# PATHOS_SOM_Ethernet.net
KiCad netlist of a schematic drawn in Altium Designer
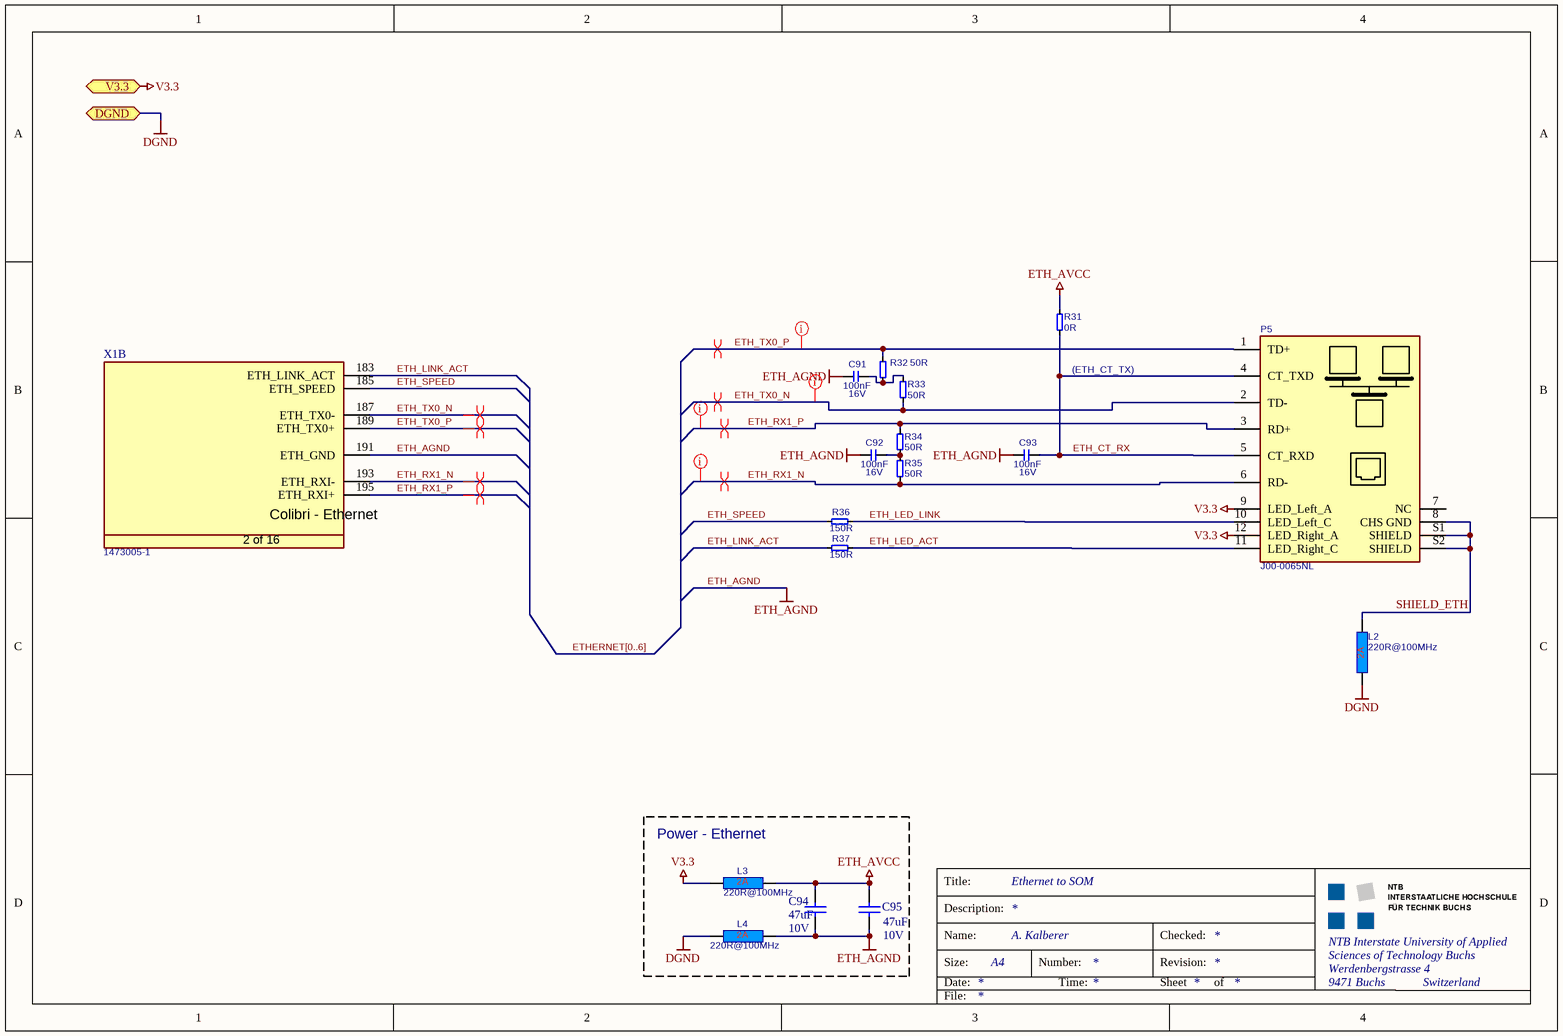
[diagram p0: PATHOS_SOM_Ethernet.SchDoc]

(export (version "E")
  (design (tool "Eeschema 10.0.6"))
  (components
    (comp (ref "C91")
      (value "100nF")
      (footprint "0603_3D")
      (description "Capacitor Ceramic X7R 100nF 16V 10% 0603")
      (fields (field (name "TOLERANCE") "10%") (field (name "RATING") "16V"))
      (libsource (lib "Viola") (part "C-X7R-100nF-16V-10%-0603"))
    )
    (comp (ref "C92")
      (value "100nF")
      (footprint "0603_3D")
      (description "Capacitor Ceramic X7R 100nF 16V 10% 0603")
      (fields (field (name "TOLERANCE") "10%") (field (name "RATING") "16V"))
      (libsource (lib "Viola") (part "C-X7R-100nF-16V-10%-0603"))
    )
    (comp (ref "C93")
      (value "100nF")
      (footprint "0603_3D")
      (description "Capacitor Ceramic X7R 100nF 16V 10% 0603")
      (fields (field (name "TOLERANCE") "10%") (field (name "RATING") "16V"))
      (libsource (lib "Viola") (part "C-X7R-100nF-16V-10%-0603"))
    )
    (comp (ref "C94")
      (value "47uF")
      (footprint "0805_3D")
      (description "Capacitor")
      (fields (field (name "VOLTAGE MAXIMUM") "10V") (field (name "#PUBLISHER") "Dr. A. Heinzelmann"))
      (libsource (lib "EFS_Sensorboard") (part "C"))
    )
    (comp (ref "C95")
      (value "47uF")
      (footprint "0805_3D")
      (description "Capacitor")
      (fields (field (name "VOLTAGE MAXIMUM") "10V") (field (name "#PUBLISHER") "Dr. A. Heinzelmann"))
      (libsource (lib "EFS_Sensorboard") (part "C"))
    )
    (comp (ref "L2")
      (value "220R@100MHz")
      (footprint "0603_3D")
      (description "220R@100MHz 2A EMI FILTER")
      (fields (field (name "TOLERANCE") "25%"))
      (libsource (lib "Viola") (part "L-220R@100MHz-2A-25%-0603"))
    )
    (comp (ref "L3")
      (value "220R@100MHz")
      (footprint "0603_3D")
      (description "220R@100MHz 2A EMI FILTER")
      (fields (field (name "TOLERANCE") "25%"))
      (libsource (lib "") (part "L-220R@100MHz-2A-25%-0603_1"))
    )
    (comp (ref "L4")
      (value "220R@100MHz")
      (footprint "0603_3D")
      (description "220R@100MHz 2A EMI FILTER")
      (fields (field (name "TOLERANCE") "25%"))
      (libsource (lib "") (part "L-220R@100MHz-2A-25%-0603_1"))
    )
    (comp (ref "P5")
      (value "J00-0065NL")
      (footprint "T_PULSE_J00-0065NL")
      (description "RJ45 Connector")
      (fields (field (name "MANUFACTURER PART NO.") "J00-0065NL"))
      (libsource (lib "Evaluation Board") (part "CON-Pulse-J00-0065NL"))
    )
    (comp (ref "R31")
      (value "0R")
      (footprint "0603_3D")
      (description "Resistor 0 ohm 100mW Jumper 0603")
      (fields (field (name "TOLERANCE") "1%"))
      (libsource (lib "Viola") (part "R-0R-100mW-JP-0603"))
    )
    (comp (ref "R32")
      (value "50R")
      (footprint "0603_3D")
      (description "Resistor 50 ohm 63mW 1% 0603")
      (fields (field (name "TOLERANCE") "1%"))
      (libsource (lib "Viola") (part "R-50R-63mW-1%-0603"))
    )
    (comp (ref "R33")
      (value "50R")
      (footprint "0603_3D")
      (description "Resistor 50 ohm 63mW 1% 0603")
      (fields (field (name "TOLERANCE") "1%"))
      (libsource (lib "Viola") (part "R-50R-63mW-1%-0603"))
    )
    (comp (ref "R34")
      (value "50R")
      (footprint "0603_3D")
      (description "Resistor 50 ohm 63mW 1% 0603")
      (fields (field (name "TOLERANCE") "1%"))
      (libsource (lib "Viola") (part "R-50R-63mW-1%-0603"))
    )
    (comp (ref "R35")
      (value "50R")
      (footprint "0603_3D")
      (description "Resistor 50 ohm 63mW 1% 0603")
      (fields (field (name "TOLERANCE") "1%"))
      (libsource (lib "Viola") (part "R-50R-63mW-1%-0603"))
    )
    (comp (ref "R36")
      (value "150R")
      (footprint "0603_3D")
      (description "Resistor 150 ohm 63mW 1% 0603")
      (fields (field (name "TOLERANCE") "1%"))
      (libsource (lib "Viola") (part "R-150R-63mW-1%-0603"))
    )
    (comp (ref "R37")
      (value "150R")
      (footprint "0603_3D")
      (description "Resistor 150 ohm 63mW 1% 0603")
      (fields (field (name "TOLERANCE") "1%"))
      (libsource (lib "Viola") (part "R-150R-63mW-1%-0603"))
    )
    (comp (ref "X1")
      (value "CON-Tyco-1473005-1-200-0.6mm")
      (footprint "T_Tyco_1473005-1")
      (description "SODIMM Connector")
      (fields (field (name "MANUFACTURER PART NO.") "1473005-1"))
      (libsource (lib "EFS_Sensorboard") (part "CON-Tyco-1473005-1-200-0.6mm"))
    )
  )
  (nets
    (net (code "9") (name "/ETH_CT_RX") (class "Default")
      (node (ref "C93") (pin "2") (pinfunction "2_2") (pintype "passive"))
      (node (ref "P5") (pin "4") (pinfunction "CT_TXD_4") (pintype "passive"))
      (node (ref "P5") (pin "5") (pinfunction "CT_RXD_5") (pintype "passive"))
      (node (ref "R31") (pin "2") (pinfunction "2_2") (pintype "passive"))
    )
    (net (code "10") (name "/ETH_LED_ACT") (class "Default")
      (node (ref "P5") (pin "11") (pinfunction "LED_Right_C_11") (pintype "passive"))
      (node (ref "R37") (pin "2") (pinfunction "2_2") (pintype "passive"))
    )
    (net (code "11") (name "/ETH_LED_LINK") (class "Default")
      (node (ref "P5") (pin "10") (pinfunction "LED_Left_C_10") (pintype "passive"))
      (node (ref "R36") (pin "2") (pinfunction "2_2") (pintype "passive"))
    )
    (net (code "12") (name "/ETH_LINK_ACT") (class "Default")
      (node (ref "R37") (pin "1") (pinfunction "1_1") (pintype "passive"))
      (node (ref "X1") (pin "183") (pinfunction "ETH_LINK_ACT_183") (pintype "passive"))
    )
    (net (code "13") (name "/ETH_RX1_N") (class "Default")
      (node (ref "P5") (pin "6") (pinfunction "RD-_6") (pintype "passive"))
      (node (ref "R35") (pin "1") (pinfunction "1_1") (pintype "passive"))
      (node (ref "X1") (pin "193") (pinfunction "ETH_RXI-_193") (pintype "passive"))
    )
    (net (code "14") (name "/ETH_RX1_P") (class "Default")
      (node (ref "P5") (pin "3") (pinfunction "RD+_3") (pintype "passive"))
      (node (ref "R34") (pin "2") (pinfunction "2_2") (pintype "passive"))
      (node (ref "X1") (pin "195") (pinfunction "ETH_RXI+_195") (pintype "passive"))
    )
    (net (code "15") (name "/ETH_SPEED") (class "Default")
      (node (ref "R36") (pin "1") (pinfunction "1_1") (pintype "passive"))
      (node (ref "X1") (pin "185") (pinfunction "ETH_SPEED_185") (pintype "passive"))
    )
    (net (code "16") (name "/ETH_TX0_N") (class "Default")
      (node (ref "P5") (pin "2") (pinfunction "TD-_2") (pintype "passive"))
      (node (ref "R33") (pin "1") (pinfunction "1_1") (pintype "passive"))
      (node (ref "X1") (pin "187") (pinfunction "ETH_TX0-_187") (pintype "passive"))
    )
    (net (code "17") (name "/ETH_TX0_P") (class "Default")
      (node (ref "P5") (pin "1") (pinfunction "TD+_1") (pintype "passive"))
      (node (ref "R32") (pin "2") (pinfunction "2_2") (pintype "passive"))
      (node (ref "X1") (pin "189") (pinfunction "ETH_TX0+_189") (pintype "passive"))
    )
    (net (code "18") (name "/SHIELD_ETH") (class "Default")
      (node (ref "L2") (pin "2") (pinfunction "2_2") (pintype "passive"))
      (node (ref "P5") (pin "8") (pinfunction "CHS_GND_8") (pintype "passive"))
      (node (ref "P5") (pin "S1") (pinfunction "SHIELD_S1") (pintype "passive"))
      (node (ref "P5") (pin "S2") (pinfunction "SHIELD_S2") (pintype "passive"))
    )
    (net (code "19") (name "DGND") (class "Default")
      (node (ref "L2") (pin "1") (pinfunction "1_1") (pintype "passive"))
      (node (ref "L4") (pin "1") (pinfunction "1_1") (pintype "passive"))
    )
    (net (code "20") (name "ETH_AGND") (class "Default")
      (node (ref "C91") (pin "1") (pinfunction "1_1") (pintype "passive"))
      (node (ref "C92") (pin "1") (pinfunction "1_1") (pintype "passive"))
      (node (ref "C93") (pin "1") (pinfunction "1_1") (pintype "passive"))
      (node (ref "C94") (pin "1") (pinfunction "1_1") (pintype "passive"))
      (node (ref "C95") (pin "1") (pinfunction "1_1") (pintype "passive"))
      (node (ref "L4") (pin "2") (pinfunction "2_2") (pintype "passive"))
      (node (ref "X1") (pin "191") (pinfunction "ETH_GND_191") (pintype "passive"))
    )
    (net (code "21") (name "ETH_AVCC") (class "Default")
      (node (ref "C94") (pin "2") (pinfunction "2_2") (pintype "passive"))
      (node (ref "C95") (pin "2") (pinfunction "2_2") (pintype "passive"))
      (node (ref "L3") (pin "2") (pinfunction "2_2") (pintype "passive"))
      (node (ref "R31") (pin "1") (pinfunction "1_1") (pintype "passive"))
    )
    (net (code "22") (name "Net-(C91-Pad2)") (class "Default")
      (node (ref "C91") (pin "2") (pinfunction "2_2") (pintype "passive"))
      (node (ref "R32") (pin "1") (pinfunction "1_1") (pintype "passive"))
      (node (ref "R33") (pin "2") (pinfunction "2_2") (pintype "passive"))
    )
    (net (code "23") (name "Net-(C92-Pad2)") (class "Default")
      (node (ref "C92") (pin "2") (pinfunction "2_2") (pintype "passive"))
      (node (ref "R34") (pin "1") (pinfunction "1_1") (pintype "passive"))
      (node (ref "R35") (pin "2") (pinfunction "2_2") (pintype "passive"))
    )
    (net (code "24") (name "V3.3") (class "Default")
      (node (ref "L3") (pin "1") (pinfunction "1_1") (pintype "passive"))
      (node (ref "P5") (pin "12") (pinfunction "LED_Right_A_12") (pintype "passive"))
      (node (ref "P5") (pin "9") (pinfunction "LED_Left_A_9") (pintype "passive"))
    )
    (net (code "25") (name "unconnected-(P5-NC-Pad7)") (class "Default")
      (node (ref "P5") (pin "7") (pinfunction "NC_7") (pintype "passive"))
    )
  )
)
